# 06_-_MEMORY.net
KiCad netlist of a schematic drawn in Altium Designer
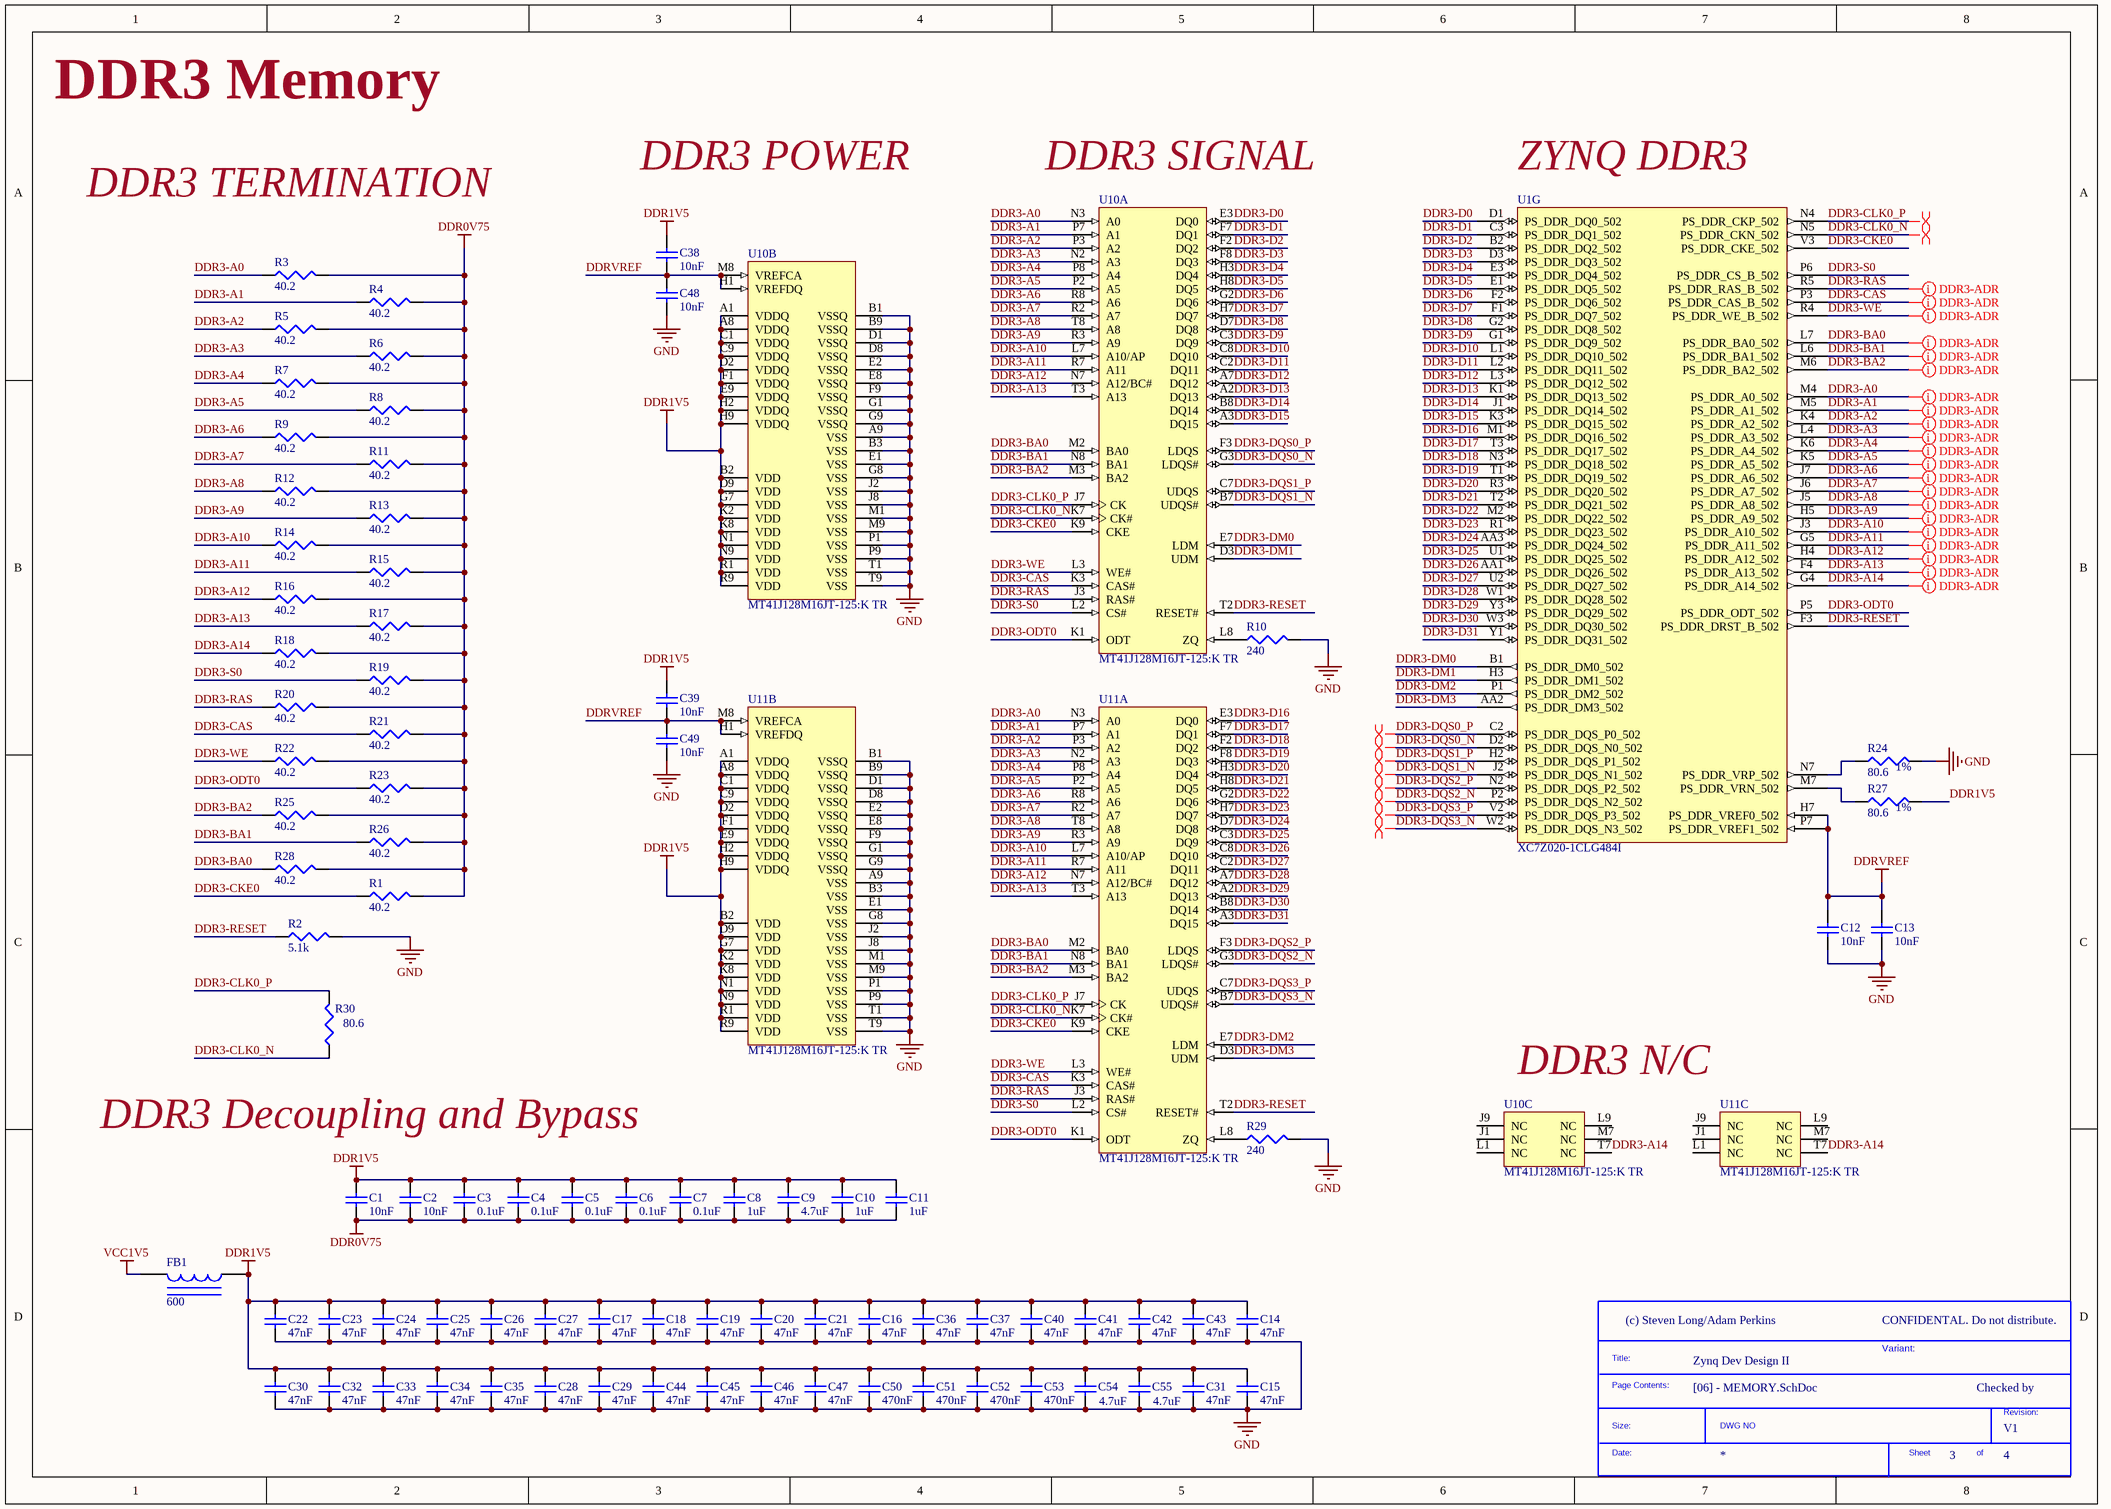
[diagram p0: [06] - MEMORY.SchDoc]

(export (version "E")
  (design (tool "Eeschema 10.0.6"))
  (components
    (comp (ref "C1")
      (value "10nF")
      (footprint "0402")
      (description "Capacitor (Semiconductor SIM Model)")
      (fields (field (name "Comment") "Capacitor") (field (name "PUBLISHER") "Altium Limited"))
      (libsource (lib "Miscellaneous Devices") (part "Cap Semi"))
    )
    (comp (ref "C2")
      (value "10nF")
      (footprint "0402")
      (description "Capacitor (Semiconductor SIM Model)")
      (fields (field (name "Comment") "Capacitor") (field (name "PUBLISHER") "Altium Limited"))
      (libsource (lib "Miscellaneous Devices") (part "Cap Semi"))
    )
    (comp (ref "C3")
      (value "0.1uF")
      (footprint "0402")
      (description "Capacitor (Semiconductor SIM Model)")
      (fields (field (name "Comment") "Capacitor") (field (name "PUBLISHER") "Altium Limited"))
      (libsource (lib "Miscellaneous Devices") (part "Cap Semi"))
    )
    (comp (ref "C4")
      (value "0.1uF")
      (footprint "0402")
      (description "Capacitor (Semiconductor SIM Model)")
      (fields (field (name "Comment") "Capacitor") (field (name "PUBLISHER") "Altium Limited"))
      (libsource (lib "Miscellaneous Devices") (part "Cap Semi"))
    )
    (comp (ref "C5")
      (value "0.1uF")
      (footprint "0402")
      (description "Capacitor (Semiconductor SIM Model)")
      (fields (field (name "Comment") "Capacitor") (field (name "PUBLISHER") "Altium Limited"))
      (libsource (lib "Miscellaneous Devices") (part "Cap Semi"))
    )
    (comp (ref "C6")
      (value "0.1uF")
      (footprint "0402")
      (description "Capacitor (Semiconductor SIM Model)")
      (fields (field (name "Comment") "Capacitor") (field (name "PUBLISHER") "Altium Limited"))
      (libsource (lib "Miscellaneous Devices") (part "Cap Semi"))
    )
    (comp (ref "C7")
      (value "0.1uF")
      (footprint "0402")
      (description "Capacitor (Semiconductor SIM Model)")
      (fields (field (name "Comment") "Capacitor") (field (name "PUBLISHER") "Altium Limited"))
      (libsource (lib "Miscellaneous Devices") (part "Cap Semi"))
    )
    (comp (ref "C8")
      (value "1uF")
      (footprint "1608[0603]")
      (description "Capacitor (Semiconductor SIM Model)")
      (fields (field (name "Comment") "Capacitor") (field (name "PUBLISHER") "Altium Limited"))
      (libsource (lib "Miscellaneous Devices") (part "Cap Semi"))
    )
    (comp (ref "C9")
      (value "4.7uF")
      (footprint "1608[0603]")
      (description "Capacitor (Semiconductor SIM Model)")
      (fields (field (name "Comment") "Capacitor") (field (name "PUBLISHER") "Altium Limited"))
      (libsource (lib "Miscellaneous Devices") (part "Cap Semi"))
    )
    (comp (ref "C10")
      (value "1uF")
      (footprint "1608[0603]")
      (description "Capacitor (Semiconductor SIM Model)")
      (fields (field (name "Comment") "Capacitor") (field (name "PUBLISHER") "Altium Limited"))
      (libsource (lib "Miscellaneous Devices") (part "Cap Semi"))
    )
    (comp (ref "C11")
      (value "1uF")
      (footprint "1608[0603]")
      (description "Capacitor (Semiconductor SIM Model)")
      (fields (field (name "Comment") "Capacitor") (field (name "PUBLISHER") "Altium Limited"))
      (libsource (lib "Miscellaneous Devices") (part "Cap Semi"))
    )
    (comp (ref "C12")
      (value "10nF")
      (footprint "0402")
      (description "Capacitor (Semiconductor SIM Model)")
      (fields (field (name "Comment") "Capacitor") (field (name "PUBLISHER") "Altium Limited"))
      (libsource (lib "Miscellaneous Devices") (part "Cap Semi"))
    )
    (comp (ref "C13")
      (value "10nF")
      (footprint "0402")
      (description "Capacitor (Semiconductor SIM Model)")
      (fields (field (name "Comment") "Capacitor") (field (name "PUBLISHER") "Altium Limited"))
      (libsource (lib "Miscellaneous Devices") (part "Cap Semi"))
    )
    (comp (ref "C14")
      (value "47nF")
      (footprint "0402")
      (description "Capacitor (Semiconductor SIM Model)")
      (fields (field (name "Comment") "Capacitor") (field (name "PUBLISHER") "Altium Limited"))
      (libsource (lib "Miscellaneous Devices") (part "Cap Semi"))
    )
    (comp (ref "C15")
      (value "47nF")
      (footprint "0402")
      (description "Capacitor (Semiconductor SIM Model)")
      (fields (field (name "Comment") "Capacitor") (field (name "PUBLISHER") "Altium Limited"))
      (libsource (lib "Miscellaneous Devices") (part "Cap Semi"))
    )
    (comp (ref "C16")
      (value "47nF")
      (footprint "0402")
      (description "Capacitor (Semiconductor SIM Model)")
      (fields (field (name "Comment") "Capacitor") (field (name "PUBLISHER") "Altium Limited"))
      (libsource (lib "Miscellaneous Devices") (part "Cap Semi"))
    )
    (comp (ref "C17")
      (value "47nF")
      (footprint "0402")
      (description "Capacitor (Semiconductor SIM Model)")
      (fields (field (name "Comment") "Capacitor") (field (name "PUBLISHER") "Altium Limited"))
      (libsource (lib "Miscellaneous Devices") (part "Cap Semi"))
    )
    (comp (ref "C18")
      (value "47nF")
      (footprint "0402")
      (description "Capacitor (Semiconductor SIM Model)")
      (fields (field (name "Comment") "Capacitor") (field (name "PUBLISHER") "Altium Limited"))
      (libsource (lib "Miscellaneous Devices") (part "Cap Semi"))
    )
    (comp (ref "C19")
      (value "47nF")
      (footprint "0402")
      (description "Capacitor (Semiconductor SIM Model)")
      (fields (field (name "Comment") "Capacitor") (field (name "PUBLISHER") "Altium Limited"))
      (libsource (lib "Miscellaneous Devices") (part "Cap Semi"))
    )
    (comp (ref "C20")
      (value "47nF")
      (footprint "0402")
      (description "Capacitor (Semiconductor SIM Model)")
      (fields (field (name "Comment") "Capacitor") (field (name "PUBLISHER") "Altium Limited"))
      (libsource (lib "Miscellaneous Devices") (part "Cap Semi"))
    )
    (comp (ref "C21")
      (value "47nF")
      (footprint "0402")
      (description "Capacitor (Semiconductor SIM Model)")
      (fields (field (name "Comment") "Capacitor") (field (name "PUBLISHER") "Altium Limited"))
      (libsource (lib "Miscellaneous Devices") (part "Cap Semi"))
    )
    (comp (ref "C22")
      (value "47nF")
      (footprint "0402")
      (description "Capacitor (Semiconductor SIM Model)")
      (fields (field (name "Comment") "Capacitor") (field (name "PUBLISHER") "Altium Limited"))
      (libsource (lib "Miscellaneous Devices") (part "Cap Semi"))
    )
    (comp (ref "C23")
      (value "47nF")
      (footprint "0402")
      (description "Capacitor (Semiconductor SIM Model)")
      (fields (field (name "Comment") "Capacitor") (field (name "PUBLISHER") "Altium Limited"))
      (libsource (lib "Miscellaneous Devices") (part "Cap Semi"))
    )
    (comp (ref "C24")
      (value "47nF")
      (footprint "0402")
      (description "Capacitor (Semiconductor SIM Model)")
      (fields (field (name "Comment") "Capacitor") (field (name "PUBLISHER") "Altium Limited"))
      (libsource (lib "Miscellaneous Devices") (part "Cap Semi"))
    )
    (comp (ref "C25")
      (value "47nF")
      (footprint "0402")
      (description "Capacitor (Semiconductor SIM Model)")
      (fields (field (name "Comment") "Capacitor") (field (name "PUBLISHER") "Altium Limited"))
      (libsource (lib "Miscellaneous Devices") (part "Cap Semi"))
    )
    (comp (ref "C26")
      (value "47nF")
      (footprint "0402")
      (description "Capacitor (Semiconductor SIM Model)")
      (fields (field (name "Comment") "Capacitor") (field (name "PUBLISHER") "Altium Limited"))
      (libsource (lib "Miscellaneous Devices") (part "Cap Semi"))
    )
    (comp (ref "C27")
      (value "47nF")
      (footprint "0402")
      (description "Capacitor (Semiconductor SIM Model)")
      (fields (field (name "Comment") "Capacitor") (field (name "PUBLISHER") "Altium Limited"))
      (libsource (lib "Miscellaneous Devices") (part "Cap Semi"))
    )
    (comp (ref "C28")
      (value "47nF")
      (footprint "0402")
      (description "Capacitor (Semiconductor SIM Model)")
      (fields (field (name "Comment") "Capacitor") (field (name "PUBLISHER") "Altium Limited"))
      (libsource (lib "Miscellaneous Devices") (part "Cap Semi"))
    )
    (comp (ref "C29")
      (value "47nF")
      (footprint "0402")
      (description "Capacitor (Semiconductor SIM Model)")
      (fields (field (name "Comment") "Capacitor") (field (name "PUBLISHER") "Altium Limited"))
      (libsource (lib "Miscellaneous Devices") (part "Cap Semi"))
    )
    (comp (ref "C30")
      (value "47nF")
      (footprint "0402")
      (description "Capacitor (Semiconductor SIM Model)")
      (fields (field (name "Comment") "Capacitor") (field (name "PUBLISHER") "Altium Limited"))
      (libsource (lib "Miscellaneous Devices") (part "Cap Semi"))
    )
    (comp (ref "C31")
      (value "47nF")
      (footprint "0402")
      (description "Capacitor (Semiconductor SIM Model)")
      (fields (field (name "Comment") "Capacitor") (field (name "PUBLISHER") "Altium Limited"))
      (libsource (lib "Miscellaneous Devices") (part "Cap Semi"))
    )
    (comp (ref "C32")
      (value "47nF")
      (footprint "0402")
      (description "Capacitor (Semiconductor SIM Model)")
      (fields (field (name "Comment") "Capacitor") (field (name "PUBLISHER") "Altium Limited"))
      (libsource (lib "Miscellaneous Devices") (part "Cap Semi"))
    )
    (comp (ref "C33")
      (value "47nF")
      (footprint "0402")
      (description "Capacitor (Semiconductor SIM Model)")
      (fields (field (name "Comment") "Capacitor") (field (name "PUBLISHER") "Altium Limited"))
      (libsource (lib "Miscellaneous Devices") (part "Cap Semi"))
    )
    (comp (ref "C34")
      (value "47nF")
      (footprint "0402")
      (description "Capacitor (Semiconductor SIM Model)")
      (fields (field (name "Comment") "Capacitor") (field (name "PUBLISHER") "Altium Limited"))
      (libsource (lib "Miscellaneous Devices") (part "Cap Semi"))
    )
    (comp (ref "C35")
      (value "47nF")
      (footprint "0402")
      (description "Capacitor (Semiconductor SIM Model)")
      (fields (field (name "Comment") "Capacitor") (field (name "PUBLISHER") "Altium Limited"))
      (libsource (lib "Miscellaneous Devices") (part "Cap Semi"))
    )
    (comp (ref "C36")
      (value "47nF")
      (footprint "0402")
      (description "Capacitor (Semiconductor SIM Model)")
      (fields (field (name "Comment") "Capacitor") (field (name "PUBLISHER") "Altium Limited"))
      (libsource (lib "Miscellaneous Devices") (part "Cap Semi"))
    )
    (comp (ref "C37")
      (value "47nF")
      (footprint "0402")
      (description "Capacitor (Semiconductor SIM Model)")
      (fields (field (name "Comment") "Capacitor") (field (name "PUBLISHER") "Altium Limited"))
      (libsource (lib "Miscellaneous Devices") (part "Cap Semi"))
    )
    (comp (ref "C38")
      (value "10nF")
      (footprint "0402")
      (description "Capacitor (Semiconductor SIM Model)")
      (fields (field (name "Comment") "Capacitor") (field (name "PUBLISHER") "Altium Limited"))
      (libsource (lib "Miscellaneous Devices") (part "Cap Semi"))
    )
    (comp (ref "C39")
      (value "10nF")
      (footprint "0402")
      (description "Capacitor (Semiconductor SIM Model)")
      (fields (field (name "Comment") "Capacitor") (field (name "PUBLISHER") "Altium Limited"))
      (libsource (lib "Miscellaneous Devices") (part "Cap Semi"))
    )
    (comp (ref "C40")
      (value "47nF")
      (footprint "0402")
      (description "Capacitor (Semiconductor SIM Model)")
      (fields (field (name "Comment") "Capacitor") (field (name "PUBLISHER") "Altium Limited"))
      (libsource (lib "Miscellaneous Devices") (part "Cap Semi"))
    )
    (comp (ref "C41")
      (value "47nF")
      (footprint "0402")
      (description "Capacitor (Semiconductor SIM Model)")
      (fields (field (name "Comment") "Capacitor") (field (name "PUBLISHER") "Altium Limited"))
      (libsource (lib "Miscellaneous Devices") (part "Cap Semi"))
    )
    (comp (ref "C42")
      (value "47nF")
      (footprint "0402")
      (description "Capacitor (Semiconductor SIM Model)")
      (fields (field (name "Comment") "Capacitor") (field (name "PUBLISHER") "Altium Limited"))
      (libsource (lib "Miscellaneous Devices") (part "Cap Semi"))
    )
    (comp (ref "C43")
      (value "47nF")
      (footprint "0402")
      (description "Capacitor (Semiconductor SIM Model)")
      (fields (field (name "Comment") "Capacitor") (field (name "PUBLISHER") "Altium Limited"))
      (libsource (lib "Miscellaneous Devices") (part "Cap Semi"))
    )
    (comp (ref "C44")
      (value "47nF")
      (footprint "0402")
      (description "Capacitor (Semiconductor SIM Model)")
      (fields (field (name "Comment") "Capacitor") (field (name "PUBLISHER") "Altium Limited"))
      (libsource (lib "Miscellaneous Devices") (part "Cap Semi"))
    )
    (comp (ref "C45")
      (value "47nF")
      (footprint "0402")
      (description "Capacitor (Semiconductor SIM Model)")
      (fields (field (name "Comment") "Capacitor") (field (name "PUBLISHER") "Altium Limited"))
      (libsource (lib "Miscellaneous Devices") (part "Cap Semi"))
    )
    (comp (ref "C46")
      (value "47nF")
      (footprint "0402")
      (description "Capacitor (Semiconductor SIM Model)")
      (fields (field (name "Comment") "Capacitor") (field (name "PUBLISHER") "Altium Limited"))
      (libsource (lib "Miscellaneous Devices") (part "Cap Semi"))
    )
    (comp (ref "C47")
      (value "47nF")
      (footprint "0402")
      (description "Capacitor (Semiconductor SIM Model)")
      (fields (field (name "Comment") "Capacitor") (field (name "PUBLISHER") "Altium Limited"))
      (libsource (lib "Miscellaneous Devices") (part "Cap Semi"))
    )
    (comp (ref "C48")
      (value "10nF")
      (footprint "0402")
      (description "Capacitor (Semiconductor SIM Model)")
      (fields (field (name "Comment") "Capacitor") (field (name "PUBLISHER") "Altium Limited"))
      (libsource (lib "Miscellaneous Devices") (part "Cap Semi"))
    )
    (comp (ref "C49")
      (value "10nF")
      (footprint "0402")
      (description "Capacitor (Semiconductor SIM Model)")
      (fields (field (name "Comment") "Capacitor") (field (name "PUBLISHER") "Altium Limited"))
      (libsource (lib "Miscellaneous Devices") (part "Cap Semi"))
    )
    (comp (ref "C50")
      (value "470nF")
      (footprint "0402")
      (description "Capacitor (Semiconductor SIM Model)")
      (fields (field (name "Comment") "Capacitor") (field (name "PUBLISHER") "Altium Limited"))
      (libsource (lib "Miscellaneous Devices") (part "Cap Semi"))
    )
    (comp (ref "C51")
      (value "470nF")
      (footprint "0402")
      (description "Capacitor (Semiconductor SIM Model)")
      (fields (field (name "Comment") "Capacitor") (field (name "PUBLISHER") "Altium Limited"))
      (libsource (lib "Miscellaneous Devices") (part "Cap Semi"))
    )
    (comp (ref "C52")
      (value "470nF")
      (footprint "0402")
      (description "Capacitor (Semiconductor SIM Model)")
      (fields (field (name "Comment") "Capacitor") (field (name "PUBLISHER") "Altium Limited"))
      (libsource (lib "Miscellaneous Devices") (part "Cap Semi"))
    )
    (comp (ref "C53")
      (value "470nF")
      (footprint "0402")
      (description "Capacitor (Semiconductor SIM Model)")
      (fields (field (name "Comment") "Capacitor") (field (name "PUBLISHER") "Altium Limited"))
      (libsource (lib "Miscellaneous Devices") (part "Cap Semi"))
    )
    (comp (ref "C54")
      (value "4.7uF")
      (footprint "1608[0603]")
      (description "Capacitor (Semiconductor SIM Model)")
      (fields (field (name "Comment") "Capacitor") (field (name "PUBLISHER") "Altium Limited"))
      (libsource (lib "Miscellaneous Devices") (part "Cap Semi"))
    )
    (comp (ref "C55")
      (value "4.7uF")
      (footprint "1608[0603]")
      (description "Capacitor (Semiconductor SIM Model)")
      (fields (field (name "Comment") "Capacitor") (field (name "PUBLISHER") "Altium Limited"))
      (libsource (lib "Miscellaneous Devices") (part "Cap Semi"))
    )
    (comp (ref "FB1")
      (value "600")
      (footprint "6-0805_N")
      (description "Magnetic-Core Inductor")
      (fields (field (name "Comment") "Ferrite Bead") (field (name "PUBLISHER") "Altium Limited"))
      (libsource (lib "Miscellaneous Devices") (part "Inductor Iron"))
    )
    (comp (ref "R1")
      (value "40.2")
      (footprint "0402")
      (description "Resistor")
      (fields (field (name "PUBLISHER") "Altium Limited"))
      (libsource (lib "Miscellaneous Devices") (part "Res3"))
    )
    (comp (ref "R2")
      (value "5.1k")
      (footprint "0402")
      (description "Resistor")
      (fields (field (name "PUBLISHER") "Altium Limited"))
      (libsource (lib "Miscellaneous Devices") (part "Res3"))
    )
    (comp (ref "R3")
      (value "40.2")
      (footprint "0402")
      (description "Resistor")
      (fields (field (name "PUBLISHER") "Altium Limited"))
      (libsource (lib "Miscellaneous Devices") (part "Res3"))
    )
    (comp (ref "R4")
      (value "40.2")
      (footprint "0402")
      (description "Resistor")
      (fields (field (name "PUBLISHER") "Altium Limited"))
      (libsource (lib "Miscellaneous Devices") (part "Res3"))
    )
    (comp (ref "R5")
      (value "40.2")
      (footprint "0402")
      (description "Resistor")
      (fields (field (name "PUBLISHER") "Altium Limited"))
      (libsource (lib "Miscellaneous Devices") (part "Res3"))
    )
    (comp (ref "R6")
      (value "40.2")
      (footprint "0402")
      (description "Resistor")
      (fields (field (name "PUBLISHER") "Altium Limited"))
      (libsource (lib "Miscellaneous Devices") (part "Res3"))
    )
    (comp (ref "R7")
      (value "40.2")
      (footprint "0402")
      (description "Resistor")
      (fields (field (name "PUBLISHER") "Altium Limited"))
      (libsource (lib "Miscellaneous Devices") (part "Res3"))
    )
    (comp (ref "R8")
      (value "40.2")
      (footprint "0402")
      (description "Resistor")
      (fields (field (name "PUBLISHER") "Altium Limited"))
      (libsource (lib "Miscellaneous Devices") (part "Res3"))
    )
    (comp (ref "R9")
      (value "40.2")
      (footprint "0402")
      (description "Resistor")
      (fields (field (name "PUBLISHER") "Altium Limited"))
      (libsource (lib "Miscellaneous Devices") (part "Res3"))
    )
    (comp (ref "R10")
      (value "240")
      (footprint "0402")
      (description "Resistor")
      (fields (field (name "PUBLISHER") "Altium Limited"))
      (libsource (lib "Miscellaneous Devices") (part "Res3"))
    )
    (comp (ref "R11")
      (value "40.2")
      (footprint "0402")
      (description "Resistor")
      (fields (field (name "PUBLISHER") "Altium Limited"))
      (libsource (lib "Miscellaneous Devices") (part "Res3"))
    )
    (comp (ref "R12")
      (value "40.2")
      (footprint "0402")
      (description "Resistor")
      (fields (field (name "PUBLISHER") "Altium Limited"))
      (libsource (lib "Miscellaneous Devices") (part "Res3"))
    )
    (comp (ref "R13")
      (value "40.2")
      (footprint "0402")
      (description "Resistor")
      (fields (field (name "PUBLISHER") "Altium Limited"))
      (libsource (lib "Miscellaneous Devices") (part "Res3"))
    )
    (comp (ref "R14")
      (value "40.2")
      (footprint "0402")
      (description "Resistor")
      (fields (field (name "PUBLISHER") "Altium Limited"))
      (libsource (lib "Miscellaneous Devices") (part "Res3"))
    )
    (comp (ref "R15")
      (value "40.2")
      (footprint "0402")
      (description "Resistor")
      (fields (field (name "PUBLISHER") "Altium Limited"))
      (libsource (lib "Miscellaneous Devices") (part "Res3"))
    )
    (comp (ref "R16")
      (value "40.2")
      (footprint "0402")
      (description "Resistor")
      (fields (field (name "PUBLISHER") "Altium Limited"))
      (libsource (lib "Miscellaneous Devices") (part "Res3"))
    )
    (comp (ref "R17")
      (value "40.2")
      (footprint "0402")
      (description "Resistor")
      (fields (field (name "PUBLISHER") "Altium Limited"))
      (libsource (lib "Miscellaneous Devices") (part "Res3"))
    )
    (comp (ref "R18")
      (value "40.2")
      (footprint "0402")
      (description "Resistor")
      (fields (field (name "PUBLISHER") "Altium Limited"))
      (libsource (lib "Miscellaneous Devices") (part "Res3"))
    )
    (comp (ref "R19")
      (value "40.2")
      (footprint "0402")
      (description "Resistor")
      (fields (field (name "PUBLISHER") "Altium Limited"))
      (libsource (lib "Miscellaneous Devices") (part "Res3"))
    )
    (comp (ref "R20")
      (value "40.2")
      (footprint "0402")
      (description "Resistor")
      (fields (field (name "PUBLISHER") "Altium Limited"))
      (libsource (lib "Miscellaneous Devices") (part "Res3"))
    )
    (comp (ref "R21")
      (value "40.2")
      (footprint "0402")
      (description "Resistor")
      (fields (field (name "PUBLISHER") "Altium Limited"))
      (libsource (lib "Miscellaneous Devices") (part "Res3"))
    )
    (comp (ref "R22")
      (value "40.2")
      (footprint "0402")
      (description "Resistor")
      (fields (field (name "PUBLISHER") "Altium Limited"))
      (libsource (lib "Miscellaneous Devices") (part "Res3"))
    )
    (comp (ref "R23")
      (value "40.2")
      (footprint "0402")
      (description "Resistor")
      (fields (field (name "PUBLISHER") "Altium Limited"))
      (libsource (lib "Miscellaneous Devices") (part "Res3"))
    )
    (comp (ref "R24")
      (value "80.6")
      (footprint "0402")
      (description "Resistor")
      (fields (field (name "TOLERANCE") "1%") (field (name "PUBLISHER") "Altium Limited"))
      (libsource (lib "Miscellaneous Devices") (part "Res3"))
    )
    (comp (ref "R25")
      (value "40.2")
      (footprint "0402")
      (description "Resistor")
      (fields (field (name "PUBLISHER") "Altium Limited"))
      (libsource (lib "Miscellaneous Devices") (part "Res3"))
    )
    (comp (ref "R26")
      (value "40.2")
      (footprint "0402")
      (description "Resistor")
      (fields (field (name "PUBLISHER") "Altium Limited"))
      (libsource (lib "Miscellaneous Devices") (part "Res3"))
    )
    (comp (ref "R27")
      (value "80.6")
      (footprint "0402")
      (description "Resistor")
      (fields (field (name "TOLERANCE") "1%") (field (name "PUBLISHER") "Altium Limited"))
      (libsource (lib "Miscellaneous Devices") (part "Res3"))
    )
    (comp (ref "R28")
      (value "40.2")
      (footprint "0402")
      (description "Resistor")
      (fields (field (name "PUBLISHER") "Altium Limited"))
      (libsource (lib "Miscellaneous Devices") (part "Res3"))
    )
    (comp (ref "R29")
      (value "240")
      (footprint "0402")
      (description "Resistor")
      (fields (field (name "PUBLISHER") "Altium Limited"))
      (libsource (lib "Miscellaneous Devices") (part "Res3"))
    )
    (comp (ref "R30")
      (value "80.6")
      (footprint "0402")
      (description "Resistor")
      (fields (field (name "TOLERANCE") "1%") (field (name "PUBLISHER") "Altium Limited"))
      (libsource (lib "Miscellaneous Devices") (part "Res3"))
    )
    (comp (ref "U1")
      (value "XC7Z020-1CLG484I")
      (footprint "CLG484")
      (description "IC SOC CORTEX-A9 ARTIX-7 484BGA")
      (fields (field (name "MANUFACTURER") "Xilinx Inc."))
      (libsource (lib "zynq_dev_V1") (part "XC7Z020-1CLG484I"))
    )
    (comp (ref "U10")
      (value "MT41J128M16JT-125:K TR")
      (footprint "MICT-JT-96")
      (description "IC DDR3 SDRAM 2GBIT 96FBGA")
      (fields (field (name "MANUFACTURER") "Micron Technology Inc."))
      (libsource (lib "zynq_dev_V1") (part "MT41J128M16JT-125{colon}K TR"))
    )
    (comp (ref "U11")
      (value "MT41J128M16JT-125:K TR")
      (footprint "MICT-JT-96")
      (description "IC DDR3 SDRAM 2GBIT 96FBGA")
      (fields (field (name "MANUFACTURER") "Micron Technology Inc."))
      (libsource (lib "zynq_dev_V1") (part "MT41J128M16JT-125{colon}K TR"))
    )
  )
  (nets
    (net (code "1") (name "/DDR3-A0") (class "Default")
      (node (ref "R3") (pin "1") (pinfunction "1_1") (pintype "passive"))
      (node (ref "U1") (pin "M4") (pinfunction "PS_DDR_A0_502_M4") (pintype "output"))
      (node (ref "U10") (pin "N3") (pinfunction "A0_N3") (pintype "input"))
      (node (ref "U11") (pin "N3") (pinfunction "A0_N3") (pintype "input"))
    )
    (net (code "2") (name "/DDR3-A1") (class "Default")
      (node (ref "R4") (pin "1") (pinfunction "1_1") (pintype "passive"))
      (node (ref "U1") (pin "M5") (pinfunction "PS_DDR_A1_502_M5") (pintype "output"))
      (node (ref "U10") (pin "P7") (pinfunction "A1_P7") (pintype "input"))
      (node (ref "U11") (pin "P7") (pinfunction "A1_P7") (pintype "input"))
    )
    (net (code "3") (name "/DDR3-A2") (class "Default")
      (node (ref "R5") (pin "1") (pinfunction "1_1") (pintype "passive"))
      (node (ref "U1") (pin "K4") (pinfunction "PS_DDR_A2_502_K4") (pintype "output"))
      (node (ref "U10") (pin "P3") (pinfunction "A2_P3") (pintype "input"))
      (node (ref "U11") (pin "P3") (pinfunction "A2_P3") (pintype "input"))
    )
    (net (code "4") (name "/DDR3-A3") (class "Default")
      (node (ref "R6") (pin "1") (pinfunction "1_1") (pintype "passive"))
      (node (ref "U1") (pin "L4") (pinfunction "PS_DDR_A3_502_L4") (pintype "output"))
      (node (ref "U10") (pin "N2") (pinfunction "A3_N2") (pintype "input"))
      (node (ref "U11") (pin "N2") (pinfunction "A3_N2") (pintype "input"))
    )
    (net (code "5") (name "/DDR3-A4") (class "Default")
      (node (ref "R7") (pin "1") (pinfunction "1_1") (pintype "passive"))
      (node (ref "U1") (pin "K6") (pinfunction "PS_DDR_A4_502_K6") (pintype "output"))
      (node (ref "U10") (pin "P8") (pinfunction "A4_P8") (pintype "input"))
      (node (ref "U11") (pin "P8") (pinfunction "A4_P8") (pintype "input"))
    )
    (net (code "6") (name "/DDR3-A5") (class "Default")
      (node (ref "R8") (pin "1") (pinfunction "1_1") (pintype "passive"))
      (node (ref "U1") (pin "K5") (pinfunction "PS_DDR_A5_502_K5") (pintype "output"))
      (node (ref "U10") (pin "P2") (pinfunction "A5_P2") (pintype "input"))
      (node (ref "U11") (pin "P2") (pinfunction "A5_P2") (pintype "input"))
    )
    (net (code "7") (name "/DDR3-A6") (class "Default")
      (node (ref "R9") (pin "1") (pinfunction "1_1") (pintype "passive"))
      (node (ref "U1") (pin "J7") (pinfunction "PS_DDR_A6_502_J7") (pintype "output"))
      (node (ref "U10") (pin "R8") (pinfunction "A6_R8") (pintype "input"))
      (node (ref "U11") (pin "R8") (pinfunction "A6_R8") (pintype "input"))
    )
    (net (code "8") (name "/DDR3-A7") (class "Default")
      (node (ref "R11") (pin "1") (pinfunction "1_1") (pintype "passive"))
      (node (ref "U1") (pin "J6") (pinfunction "PS_DDR_A7_502_J6") (pintype "output"))
      (node (ref "U10") (pin "R2") (pinfunction "A7_R2") (pintype "input"))
      (node (ref "U11") (pin "R2") (pinfunction "A7_R2") (pintype "input"))
    )
    (net (code "9") (name "/DDR3-A8") (class "Default")
      (node (ref "R12") (pin "1") (pinfunction "1_1") (pintype "passive"))
      (node (ref "U1") (pin "J5") (pinfunction "PS_DDR_A8_502_J5") (pintype "output"))
      (node (ref "U10") (pin "T8") (pinfunction "A8_T8") (pintype "input"))
      (node (ref "U11") (pin "T8") (pinfunction "A8_T8") (pintype "input"))
    )
    (net (code "10") (name "/DDR3-A9") (class "Default")
      (node (ref "R13") (pin "1") (pinfunction "1_1") (pintype "passive"))
      (node (ref "U1") (pin "H5") (pinfunction "PS_DDR_A9_502_H5") (pintype "output"))
      (node (ref "U10") (pin "R3") (pinfunction "A9_R3") (pintype "input"))
      (node (ref "U11") (pin "R3") (pinfunction "A9_R3") (pintype "input"))
    )
    (net (code "11") (name "/DDR3-A10") (class "Default")
      (node (ref "R14") (pin "1") (pinfunction "1_1") (pintype "passive"))
      (node (ref "U1") (pin "J3") (pinfunction "PS_DDR_A10_502_J3") (pintype "output"))
      (node (ref "U10") (pin "L7") (pinfunction "A10/AP_L7") (pintype "input"))
      (node (ref "U11") (pin "L7") (pinfunction "A10/AP_L7") (pintype "input"))
    )
    (net (code "12") (name "/DDR3-A11") (class "Default")
      (node (ref "R15") (pin "1") (pinfunction "1_1") (pintype "passive"))
      (node (ref "U1") (pin "G5") (pinfunction "PS_DDR_A11_502_G5") (pintype "output"))
      (node (ref "U10") (pin "R7") (pinfunction "A11_R7") (pintype "input"))
      (node (ref "U11") (pin "R7") (pinfunction "A11_R7") (pintype "input"))
    )
    (net (code "13") (name "/DDR3-A12") (class "Default")
      (node (ref "R16") (pin "1") (pinfunction "1_1") (pintype "passive"))
      (node (ref "U1") (pin "H4") (pinfunction "PS_DDR_A12_502_H4") (pintype "output"))
      (node (ref "U10") (pin "N7") (pinfunction "A12/BC#_N7") (pintype "input"))
      (node (ref "U11") (pin "N7") (pinfunction "A12/BC#_N7") (pintype "input"))
    )
    (net (code "14") (name "/DDR3-A13") (class "Default")
      (node (ref "R17") (pin "1") (pinfunction "1_1") (pintype "passive"))
      (node (ref "U1") (pin "F4") (pinfunction "PS_DDR_A13_502_F4") (pintype "output"))
      (node (ref "U10") (pin "T3") (pinfunction "A13_T3") (pintype "input"))
      (node (ref "U11") (pin "T3") (pinfunction "A13_T3") (pintype "input"))
    )
    (net (code "15") (name "/DDR3-A14") (class "Default")
      (node (ref "R18") (pin "1") (pinfunction "1_1") (pintype "passive"))
      (node (ref "U1") (pin "G4") (pinfunction "PS_DDR_A14_502_G4") (pintype "output"))
      (node (ref "U10") (pin "T7") (pinfunction "NC_T7") (pintype "passive"))
      (node (ref "U11") (pin "T7") (pinfunction "NC_T7") (pintype "passive"))
    )
    (net (code "16") (name "/DDR3-BA0") (class "Default")
      (node (ref "R28") (pin "1") (pinfunction "1_1") (pintype "passive"))
      (node (ref "U1") (pin "L7") (pinfunction "PS_DDR_BA0_502_L7") (pintype "output"))
      (node (ref "U10") (pin "M2") (pinfunction "BA0_M2") (pintype "input"))
      (node (ref "U11") (pin "M2") (pinfunction "BA0_M2") (pintype "input"))
    )
    (net (code "17") (name "/DDR3-BA1") (class "Default")
      (node (ref "R26") (pin "1") (pinfunction "1_1") (pintype "passive"))
      (node (ref "U1") (pin "L6") (pinfunction "PS_DDR_BA1_502_L6") (pintype "output"))
      (node (ref "U10") (pin "N8") (pinfunction "BA1_N8") (pintype "input"))
      (node (ref "U11") (pin "N8") (pinfunction "BA1_N8") (pintype "input"))
    )
    (net (code "18") (name "/DDR3-BA2") (class "Default")
      (node (ref "R25") (pin "1") (pinfunction "1_1") (pintype "passive"))
      (node (ref "U1") (pin "M6") (pinfunction "PS_DDR_BA2_502_M6") (pintype "output"))
      (node (ref "U10") (pin "M3") (pinfunction "BA2_M3") (pintype "input"))
      (node (ref "U11") (pin "M3") (pinfunction "BA2_M3") (pintype "input"))
    )
    (net (code "19") (name "/DDR3-CAS") (class "Default")
      (node (ref "R21") (pin "1") (pinfunction "1_1") (pintype "passive"))
      (node (ref "U1") (pin "P3") (pinfunction "PS_DDR_CAS_B_502_P3") (pintype "output"))
      (node (ref "U10") (pin "K3") (pinfunction "CAS#_K3") (pintype "input"))
      (node (ref "U11") (pin "K3") (pinfunction "CAS#_K3") (pintype "input"))
    )
    (net (code "20") (name "/DDR3-CKE0") (class "Default")
      (node (ref "R1") (pin "1") (pinfunction "1_1") (pintype "passive"))
      (node (ref "U1") (pin "V3") (pinfunction "PS_DDR_CKE_502_V3") (pintype "output"))
      (node (ref "U10") (pin "K9") (pinfunction "CKE_K9") (pintype "input"))
      (node (ref "U11") (pin "K9") (pinfunction "CKE_K9") (pintype "input"))
    )
    (net (code "21") (name "/DDR3-CLK0_N") (class "Default")
      (node (ref "R30") (pin "1") (pinfunction "1_1") (pintype "passive"))
      (node (ref "U1") (pin "N5") (pinfunction "PS_DDR_CKN_502_N5") (pintype "output"))
      (node (ref "U10") (pin "K7") (pinfunction "CK#_K7") (pintype "input"))
      (node (ref "U11") (pin "K7") (pinfunction "CK#_K7") (pintype "input"))
    )
    (net (code "22") (name "/DDR3-CLK0_P") (class "Default")
      (node (ref "R30") (pin "2") (pinfunction "2_2") (pintype "passive"))
      (node (ref "U1") (pin "N4") (pinfunction "PS_DDR_CKP_502_N4") (pintype "output"))
      (node (ref "U10") (pin "J7") (pinfunction "CK_J7") (pintype "input"))
      (node (ref "U11") (pin "J7") (pinfunction "CK_J7") (pintype "input"))
    )
    (net (code "23") (name "/DDR3-D0") (class "Default")
      (node (ref "U1") (pin "D1") (pinfunction "PS_DDR_DQ0_502_D1") (pintype "bidirectional"))
      (node (ref "U10") (pin "E3") (pinfunction "DQ0_E3") (pintype "bidirectional"))
    )
    (net (code "24") (name "/DDR3-D1") (class "Default")
      (node (ref "U1") (pin "C3") (pinfunction "PS_DDR_DQ1_502_C3") (pintype "bidirectional"))
      (node (ref "U10") (pin "F7") (pinfunction "DQ1_F7") (pintype "bidirectional"))
    )
    (net (code "25") (name "/DDR3-D2") (class "Default")
      (node (ref "U1") (pin "B2") (pinfunction "PS_DDR_DQ2_502_B2") (pintype "bidirectional"))
      (node (ref "U10") (pin "F2") (pinfunction "DQ2_F2") (pintype "bidirectional"))
    )
    (net (code "26") (name "/DDR3-D3") (class "Default")
      (node (ref "U1") (pin "D3") (pinfunction "PS_DDR_DQ3_502_D3") (pintype "bidirectional"))
      (node (ref "U10") (pin "F8") (pinfunction "DQ3_F8") (pintype "bidirectional"))
    )
    (net (code "27") (name "/DDR3-D4") (class "Default")
      (node (ref "U1") (pin "E3") (pinfunction "PS_DDR_DQ4_502_E3") (pintype "bidirectional"))
      (node (ref "U10") (pin "H3") (pinfunction "DQ4_H3") (pintype "bidirectional"))
    )
    (net (code "28") (name "/DDR3-D5") (class "Default")
      (node (ref "U1") (pin "E1") (pinfunction "PS_DDR_DQ5_502_E1") (pintype "bidirectional"))
      (node (ref "U10") (pin "H8") (pinfunction "DQ5_H8") (pintype "bidirectional"))
    )
    (net (code "29") (name "/DDR3-D6") (class "Default")
      (node (ref "U1") (pin "F2") (pinfunction "PS_DDR_DQ6_502_F2") (pintype "bidirectional"))
      (node (ref "U10") (pin "G2") (pinfunction "DQ6_G2") (pintype "bidirectional"))
    )
    (net (code "30") (name "/DDR3-D7") (class "Default")
      (node (ref "U1") (pin "F1") (pinfunction "PS_DDR_DQ7_502_F1") (pintype "bidirectional"))
      (node (ref "U10") (pin "H7") (pinfunction "DQ7_H7") (pintype "bidirectional"))
    )
    (net (code "31") (name "/DDR3-D8") (class "Default")
      (node (ref "U1") (pin "G2") (pinfunction "PS_DDR_DQ8_502_G2") (pintype "bidirectional"))
      (node (ref "U10") (pin "D7") (pinfunction "DQ8_D7") (pintype "bidirectional"))
    )
    (net (code "32") (name "/DDR3-D9") (class "Default")
      (node (ref "U1") (pin "G1") (pinfunction "PS_DDR_DQ9_502_G1") (pintype "bidirectional"))
      (node (ref "U10") (pin "C3") (pinfunction "DQ9_C3") (pintype "bidirectional"))
    )
    (net (code "33") (name "/DDR3-D10") (class "Default")
      (node (ref "U1") (pin "L1") (pinfunction "PS_DDR_DQ10_502_L1") (pintype "bidirectional"))
      (node (ref "U10") (pin "C8") (pinfunction "DQ10_C8") (pintype "bidirectional"))
    )
    (net (code "34") (name "/DDR3-D11") (class "Default")
      (node (ref "U1") (pin "L2") (pinfunction "PS_DDR_DQ11_502_L2") (pintype "bidirectional"))
      (node (ref "U10") (pin "C2") (pinfunction "DQ11_C2") (pintype "bidirectional"))
    )
    (net (code "35") (name "/DDR3-D12") (class "Default")
      (node (ref "U1") (pin "L3") (pinfunction "PS_DDR_DQ12_502_L3") (pintype "bidirectional"))
      (node (ref "U10") (pin "A7") (pinfunction "DQ12_A7") (pintype "bidirectional"))
    )
    (net (code "36") (name "/DDR3-D13") (class "Default")
      (node (ref "U1") (pin "K1") (pinfunction "PS_DDR_DQ13_502_K1") (pintype "bidirectional"))
      (node (ref "U10") (pin "A2") (pinfunction "DQ13_A2") (pintype "bidirectional"))
    )
    (net (code "37") (name "/DDR3-D14") (class "Default")
      (node (ref "U1") (pin "J1") (pinfunction "PS_DDR_DQ14_502_J1") (pintype "bidirectional"))
      (node (ref "U10") (pin "B8") (pinfunction "DQ14_B8") (pintype "bidirectional"))
    )
    (net (code "38") (name "/DDR3-D15") (class "Default")
      (node (ref "U1") (pin "K3") (pinfunction "PS_DDR_DQ15_502_K3") (pintype "bidirectional"))
      (node (ref "U10") (pin "A3") (pinfunction "DQ15_A3") (pintype "bidirectional"))
    )
    (net (code "39") (name "/DDR3-D16") (class "Default")
      (node (ref "U1") (pin "M1") (pinfunction "PS_DDR_DQ16_502_M1") (pintype "bidirectional"))
      (node (ref "U11") (pin "E3") (pinfunction "DQ0_E3") (pintype "bidirectional"))
    )
    (net (code "40") (name "/DDR3-D17") (class "Default")
      (node (ref "U1") (pin "T3") (pinfunction "PS_DDR_DQ17_502_T3") (pintype "bidirectional"))
      (node (ref "U11") (pin "F7") (pinfunction "DQ1_F7") (pintype "bidirectional"))
    )
    (net (code "41") (name "/DDR3-D18") (class "Default")
      (node (ref "U1") (pin "N3") (pinfunction "PS_DDR_DQ18_502_N3") (pintype "bidirectional"))
      (node (ref "U11") (pin "F2") (pinfunction "DQ2_F2") (pintype "bidirectional"))
    )
    (net (code "42") (name "/DDR3-D19") (class "Default")
      (node (ref "U1") (pin "T1") (pinfunction "PS_DDR_DQ19_502_T1") (pintype "bidirectional"))
      (node (ref "U11") (pin "F8") (pinfunction "DQ3_F8") (pintype "bidirectional"))
    )
    (net (code "43") (name "/DDR3-D20") (class "Default")
      (node (ref "U1") (pin "R3") (pinfunction "PS_DDR_DQ20_502_R3") (pintype "bidirectional"))
      (node (ref "U11") (pin "H3") (pinfunction "DQ4_H3") (pintype "bidirectional"))
    )
    (net (code "44") (name "/DDR3-D21") (class "Default")
      (node (ref "U1") (pin "T2") (pinfunction "PS_DDR_DQ21_502_T2") (pintype "bidirectional"))
      (node (ref "U11") (pin "H8") (pinfunction "DQ5_H8") (pintype "bidirectional"))
    )
    (net (code "45") (name "/DDR3-D22") (class "Default")
      (node (ref "U1") (pin "M2") (pinfunction "PS_DDR_DQ22_502_M2") (pintype "bidirectional"))
      (node (ref "U11") (pin "G2") (pinfunction "DQ6_G2") (pintype "bidirectional"))
    )
    (net (code "46") (name "/DDR3-D23") (class "Default")
      (node (ref "U1") (pin "R1") (pinfunction "PS_DDR_DQ23_502_R1") (pintype "bidirectional"))
      (node (ref "U11") (pin "H7") (pinfunction "DQ7_H7") (pintype "bidirectional"))
    )
    (net (code "47") (name "/DDR3-D24") (class "Default")
      (node (ref "U1") (pin "AA3") (pinfunction "PS_DDR_DQ24_502_AA3") (pintype "bidirectional"))
      (node (ref "U11") (pin "D7") (pinfunction "DQ8_D7") (pintype "bidirectional"))
    )
    (net (code "48") (name "/DDR3-D25") (class "Default")
      (node (ref "U1") (pin "U1") (pinfunction "PS_DDR_DQ25_502_U1") (pintype "bidirectional"))
      (node (ref "U11") (pin "C3") (pinfunction "DQ9_C3") (pintype "bidirectional"))
    )
    (net (code "49") (name "/DDR3-D26") (class "Default")
      (node (ref "U1") (pin "AA1") (pinfunction "PS_DDR_DQ26_502_AA1") (pintype "bidirectional"))
      (node (ref "U11") (pin "C8") (pinfunction "DQ10_C8") (pintype "bidirectional"))
    )
    (net (code "50") (name "/DDR3-D27") (class "Default")
      (node (ref "U1") (pin "U2") (pinfunction "PS_DDR_DQ27_502_U2") (pintype "bidirectional"))
      (node (ref "U11") (pin "C2") (pinfunction "DQ11_C2") (pintype "bidirectional"))
    )
    (net (code "51") (name "/DDR3-D28") (class "Default")
      (node (ref "U1") (pin "W1") (pinfunction "PS_DDR_DQ28_502_W1") (pintype "bidirectional"))
      (node (ref "U11") (pin "A7") (pinfunction "DQ12_A7") (pintype "bidirectional"))
    )
    (net (code "52") (name "/DDR3-D29") (class "Default")
      (node (ref "U1") (pin "Y3") (pinfunction "PS_DDR_DQ29_502_Y3") (pintype "bidirectional"))
      (node (ref "U11") (pin "A2") (pinfunction "DQ13_A2") (pintype "bidirectional"))
    )
    (net (code "53") (name "/DDR3-D30") (class "Default")
      (node (ref "U1") (pin "W3") (pinfunction "PS_DDR_DQ30_502_W3") (pintype "bidirectional"))
      (node (ref "U11") (pin "B8") (pinfunction "DQ14_B8") (pintype "bidirectional"))
    )
    (net (code "54") (name "/DDR3-D31") (class "Default")
      (node (ref "U1") (pin "Y1") (pinfunction "PS_DDR_DQ31_502_Y1") (pintype "bidirectional"))
      (node (ref "U11") (pin "A3") (pinfunction "DQ15_A3") (pintype "bidirectional"))
    )
    (net (code "55") (name "/DDR3-DM0") (class "Default")
      (node (ref "U1") (pin "B1") (pinfunction "PS_DDR_DM0_502_B1") (pintype "output"))
      (node (ref "U10") (pin "E7") (pinfunction "LDM_E7") (pintype "input"))
    )
    (net (code "56") (name "/DDR3-DM1") (class "Default")
      (node (ref "U1") (pin "H3") (pinfunction "PS_DDR_DM1_502_H3") (pintype "output"))
      (node (ref "U10") (pin "D3") (pinfunction "UDM_D3") (pintype "input"))
    )
    (net (code "57") (name "/DDR3-DM2") (class "Default")
      (node (ref "U1") (pin "P1") (pinfunction "PS_DDR_DM2_502_P1") (pintype "output"))
      (node (ref "U11") (pin "E7") (pinfunction "LDM_E7") (pintype "input"))
    )
    (net (code "58") (name "/DDR3-DM3") (class "Default")
      (node (ref "U1") (pin "AA2") (pinfunction "PS_DDR_DM3_502_AA2") (pintype "output"))
      (node (ref "U11") (pin "D3") (pinfunction "UDM_D3") (pintype "input"))
    )
    (net (code "59") (name "/DDR3-DQS0_N") (class "Default")
      (node (ref "U1") (pin "D2") (pinfunction "PS_DDR_DQS_N0_502_D2") (pintype "bidirectional"))
      (node (ref "U10") (pin "G3") (pinfunction "LDQS#_G3") (pintype "bidirectional"))
    )
    (net (code "60") (name "/DDR3-DQS0_P") (class "Default")
      (node (ref "U1") (pin "C2") (pinfunction "PS_DDR_DQS_P0_502_C2") (pintype "bidirectional"))
      (node (ref "U10") (pin "F3") (pinfunction "LDQS_F3") (pintype "bidirectional"))
    )
    (net (code "61") (name "/DDR3-DQS1_N") (class "Default")
      (node (ref "U1") (pin "J2") (pinfunction "PS_DDR_DQS_N1_502_J2") (pintype "bidirectional"))
      (node (ref "U10") (pin "B7") (pinfunction "UDQS#_B7") (pintype "bidirectional"))
    )
    (net (code "62") (name "/DDR3-DQS1_P") (class "Default")
      (node (ref "U1") (pin "H2") (pinfunction "PS_DDR_DQS_P1_502_H2") (pintype "bidirectional"))
      (node (ref "U10") (pin "C7") (pinfunction "UDQS_C7") (pintype "bidirectional"))
    )
    (net (code "63") (name "/DDR3-DQS2_N") (class "Default")
      (node (ref "U1") (pin "P2") (pinfunction "PS_DDR_DQS_N2_502_P2") (pintype "bidirectional"))
      (node (ref "U11") (pin "G3") (pinfunction "LDQS#_G3") (pintype "bidirectional"))
    )
    (net (code "64") (name "/DDR3-DQS2_P") (class "Default")
      (node (ref "U1") (pin "N2") (pinfunction "PS_DDR_DQS_P2_502_N2") (pintype "bidirectional"))
      (node (ref "U11") (pin "F3") (pinfunction "LDQS_F3") (pintype "bidirectional"))
    )
    (net (code "65") (name "/DDR3-DQS3_N") (class "Default")
      (node (ref "U1") (pin "W2") (pinfunction "PS_DDR_DQS_N3_502_W2") (pintype "bidirectional"))
      (node (ref "U11") (pin "B7") (pinfunction "UDQS#_B7") (pintype "bidirectional"))
    )
    (net (code "66") (name "/DDR3-DQS3_P") (class "Default")
      (node (ref "U1") (pin "V2") (pinfunction "PS_DDR_DQS_P3_502_V2") (pintype "bidirectional"))
      (node (ref "U11") (pin "C7") (pinfunction "UDQS_C7") (pintype "bidirectional"))
    )
    (net (code "67") (name "/DDR3-ODT0") (class "Default")
      (node (ref "R23") (pin "1") (pinfunction "1_1") (pintype "passive"))
      (node (ref "U1") (pin "P5") (pinfunction "PS_DDR_ODT_502_P5") (pintype "output"))
      (node (ref "U10") (pin "K1") (pinfunction "ODT_K1") (pintype "input"))
      (node (ref "U11") (pin "K1") (pinfunction "ODT_K1") (pintype "input"))
    )
    (net (code "68") (name "/DDR3-RAS") (class "Default")
      (node (ref "R20") (pin "1") (pinfunction "1_1") (pintype "passive"))
      (node (ref "U1") (pin "R5") (pinfunction "PS_DDR_RAS_B_502_R5") (pintype "output"))
      (node (ref "U10") (pin "J3") (pinfunction "RAS#_J3") (pintype "input"))
      (node (ref "U11") (pin "J3") (pinfunction "RAS#_J3") (pintype "input"))
    )
    (net (code "69") (name "/DDR3-RESET") (class "Default")
      (node (ref "R2") (pin "1") (pinfunction "1_1") (pintype "passive"))
      (node (ref "U1") (pin "F3") (pinfunction "PS_DDR_DRST_B_502_F3") (pintype "output"))
      (node (ref "U10") (pin "T2") (pinfunction "RESET#_T2") (pintype "input"))
      (node (ref "U11") (pin "T2") (pinfunction "RESET#_T2") (pintype "input"))
    )
    (net (code "70") (name "/DDR3-S0") (class "Default")
      (node (ref "R19") (pin "1") (pinfunction "1_1") (pintype "passive"))
      (node (ref "U1") (pin "P6") (pinfunction "PS_DDR_CS_B_502_P6") (pintype "output"))
      (node (ref "U10") (pin "L2") (pinfunction "CS#_L2") (pintype "input"))
      (node (ref "U11") (pin "L2") (pinfunction "CS#_L2") (pintype "input"))
    )
    (net (code "71") (name "/DDR3-WE") (class "Default")
      (node (ref "R22") (pin "1") (pinfunction "1_1") (pintype "passive"))
      (node (ref "U1") (pin "R4") (pinfunction "PS_DDR_WE_B_502_R4") (pintype "output"))
      (node (ref "U10") (pin "L3") (pinfunction "WE#_L3") (pintype "input"))
      (node (ref "U11") (pin "L3") (pinfunction "WE#_L3") (pintype "input"))
    )
    (net (code "72") (name "DDR0V75") (class "Default")
      (node (ref "C1") (pin "1") (pinfunction "1_1") (pintype "passive"))
      (node (ref "C10") (pin "1") (pinfunction "1_1") (pintype "passive"))
      (node (ref "C11") (pin "1") (pinfunction "1_1") (pintype "passive"))
      (node (ref "C2") (pin "1") (pinfunction "1_1") (pintype "passive"))
      (node (ref "C3") (pin "1") (pinfunction "1_1") (pintype "passive"))
      (node (ref "C4") (pin "1") (pinfunction "1_1") (pintype "passive"))
      (node (ref "C5") (pin "1") (pinfunction "1_1") (pintype "passive"))
      (node (ref "C6") (pin "1") (pinfunction "1_1") (pintype "passive"))
      (node (ref "C7") (pin "1") (pinfunction "1_1") (pintype "passive"))
      (node (ref "C8") (pin "1") (pinfunction "1_1") (pintype "passive"))
      (node (ref "C9") (pin "1") (pinfunction "1_1") (pintype "passive"))
      (node (ref "R1") (pin "2") (pinfunction "2_2") (pintype "passive"))
      (node (ref "R11") (pin "2") (pinfunction "2_2") (pintype "passive"))
      (node (ref "R12") (pin "2") (pinfunction "2_2") (pintype "passive"))
      (node (ref "R13") (pin "2") (pinfunction "2_2") (pintype "passive"))
      (node (ref "R14") (pin "2") (pinfunction "2_2") (pintype "passive"))
      (node (ref "R15") (pin "2") (pinfunction "2_2") (pintype "passive"))
      (node (ref "R16") (pin "2") (pinfunction "2_2") (pintype "passive"))
      (node (ref "R17") (pin "2") (pinfunction "2_2") (pintype "passive"))
      (node (ref "R18") (pin "2") (pinfunction "2_2") (pintype "passive"))
      (node (ref "R19") (pin "2") (pinfunction "2_2") (pintype "passive"))
      (node (ref "R20") (pin "2") (pinfunction "2_2") (pintype "passive"))
      (node (ref "R21") (pin "2") (pinfunction "2_2") (pintype "passive"))
      (node (ref "R22") (pin "2") (pinfunction "2_2") (pintype "passive"))
      (node (ref "R23") (pin "2") (pinfunction "2_2") (pintype "passive"))
      (node (ref "R25") (pin "2") (pinfunction "2_2") (pintype "passive"))
      (node (ref "R26") (pin "2") (pinfunction "2_2") (pintype "passive"))
      (node (ref "R28") (pin "2") (pinfunction "2_2") (pintype "passive"))
      (node (ref "R3") (pin "2") (pinfunction "2_2") (pintype "passive"))
      (node (ref "R4") (pin "2") (pinfunction "2_2") (pintype "passive"))
      (node (ref "R5") (pin "2") (pinfunction "2_2") (pintype "passive"))
      (node (ref "R6") (pin "2") (pinfunction "2_2") (pintype "passive"))
      (node (ref "R7") (pin "2") (pinfunction "2_2") (pintype "passive"))
      (node (ref "R8") (pin "2") (pinfunction "2_2") (pintype "passive"))
      (node (ref "R9") (pin "2") (pinfunction "2_2") (pintype "passive"))
    )
    (net (code "73") (name "DDR1V5") (class "Default")
      (node (ref "C1") (pin "2") (pinfunction "2_2") (pintype "passive"))
      (node (ref "C10") (pin "2") (pinfunction "2_2") (pintype "passive"))
      (node (ref "C11") (pin "2") (pinfunction "2_2") (pintype "passive"))
      (node (ref "C14") (pin "2") (pinfunction "2_2") (pintype "passive"))
      (node (ref "C15") (pin "2") (pinfunction "2_2") (pintype "passive"))
      (node (ref "C16") (pin "2") (pinfunction "2_2") (pintype "passive"))
      (node (ref "C17") (pin "2") (pinfunction "2_2") (pintype "passive"))
      (node (ref "C18") (pin "2") (pinfunction "2_2") (pintype "passive"))
      (node (ref "C19") (pin "2") (pinfunction "2_2") (pintype "passive"))
      (node (ref "C2") (pin "2") (pinfunction "2_2") (pintype "passive"))
      (node (ref "C20") (pin "2") (pinfunction "2_2") (pintype "passive"))
      (node (ref "C21") (pin "2") (pinfunction "2_2") (pintype "passive"))
      (node (ref "C22") (pin "2") (pinfunction "2_2") (pintype "passive"))
      (node (ref "C23") (pin "2") (pinfunction "2_2") (pintype "passive"))
      (node (ref "C24") (pin "2") (pinfunction "2_2") (pintype "passive"))
      (node (ref "C25") (pin "2") (pinfunction "2_2") (pintype "passive"))
      (node (ref "C26") (pin "2") (pinfunction "2_2") (pintype "passive"))
      (node (ref "C27") (pin "2") (pinfunction "2_2") (pintype "passive"))
      (node (ref "C28") (pin "2") (pinfunction "2_2") (pintype "passive"))
      (node (ref "C29") (pin "2") (pinfunction "2_2") (pintype "passive"))
      (node (ref "C3") (pin "2") (pinfunction "2_2") (pintype "passive"))
      (node (ref "C30") (pin "2") (pinfunction "2_2") (pintype "passive"))
      (node (ref "C31") (pin "2") (pinfunction "2_2") (pintype "passive"))
      (node (ref "C32") (pin "2") (pinfunction "2_2") (pintype "passive"))
      (node (ref "C33") (pin "2") (pinfunction "2_2") (pintype "passive"))
      (node (ref "C34") (pin "2") (pinfunction "2_2") (pintype "passive"))
      (node (ref "C35") (pin "2") (pinfunction "2_2") (pintype "passive"))
      (node (ref "C36") (pin "2") (pinfunction "2_2") (pintype "passive"))
      (node (ref "C37") (pin "2") (pinfunction "2_2") (pintype "passive"))
      (node (ref "C38") (pin "2") (pinfunction "2_2") (pintype "passive"))
      (node (ref "C39") (pin "2") (pinfunction "2_2") (pintype "passive"))
      (node (ref "C4") (pin "2") (pinfunction "2_2") (pintype "passive"))
      (node (ref "C40") (pin "2") (pinfunction "2_2") (pintype "passive"))
      (node (ref "C41") (pin "2") (pinfunction "2_2") (pintype "passive"))
      (node (ref "C42") (pin "2") (pinfunction "2_2") (pintype "passive"))
      (node (ref "C43") (pin "2") (pinfunction "2_2") (pintype "passive"))
      (node (ref "C44") (pin "2") (pinfunction "2_2") (pintype "passive"))
      (node (ref "C45") (pin "2") (pinfunction "2_2") (pintype "passive"))
      (node (ref "C46") (pin "2") (pinfunction "2_2") (pintype "passive"))
      (node (ref "C47") (pin "2") (pinfunction "2_2") (pintype "passive"))
      (node (ref "C5") (pin "2") (pinfunction "2_2") (pintype "passive"))
      (node (ref "C50") (pin "2") (pinfunction "2_2") (pintype "passive"))
      (node (ref "C51") (pin "2") (pinfunction "2_2") (pintype "passive"))
      (node (ref "C52") (pin "2") (pinfunction "2_2") (pintype "passive"))
      (node (ref "C53") (pin "2") (pinfunction "2_2") (pintype "passive"))
      (node (ref "C54") (pin "2") (pinfunction "2_2") (pintype "passive"))
      (node (ref "C55") (pin "2") (pinfunction "2_2") (pintype "passive"))
      (node (ref "C6") (pin "2") (pinfunction "2_2") (pintype "passive"))
      (node (ref "C7") (pin "2") (pinfunction "2_2") (pintype "passive"))
      (node (ref "C8") (pin "2") (pinfunction "2_2") (pintype "passive"))
      (node (ref "C9") (pin "2") (pinfunction "2_2") (pintype "passive"))
      (node (ref "FB1") (pin "1") (pinfunction "1_1") (pintype "passive"))
      (node (ref "R27") (pin "2") (pinfunction "2_2") (pintype "passive"))
      (node (ref "U10") (pin "A1") (pinfunction "VDDQ_A1") (pintype "power_in"))
      (node (ref "U10") (pin "A8") (pinfunction "VDDQ_A8") (pintype "power_in"))
      (node (ref "U10") (pin "B2") (pinfunction "VDD_B2") (pintype "power_in"))
      (node (ref "U10") (pin "C1") (pinfunction "VDDQ_C1") (pintype "power_in"))
      (node (ref "U10") (pin "C9") (pinfunction "VDDQ_C9") (pintype "power_in"))
      (node (ref "U10") (pin "D2") (pinfunction "VDDQ_D2") (pintype "power_in"))
      (node (ref "U10") (pin "D9") (pinfunction "VDD_D9") (pintype "power_in"))
      (node (ref "U10") (pin "E9") (pinfunction "VDDQ_E9") (pintype "power_in"))
      (node (ref "U10") (pin "F1") (pinfunction "VDDQ_F1") (pintype "power_in"))
      (node (ref "U10") (pin "G7") (pinfunction "VDD_G7") (pintype "power_in"))
      (node (ref "U10") (pin "H2") (pinfunction "VDDQ_H2") (pintype "power_in"))
      (node (ref "U10") (pin "H9") (pinfunction "VDDQ_H9") (pintype "power_in"))
      (node (ref "U10") (pin "K2") (pinfunction "VDD_K2") (pintype "power_in"))
      (node (ref "U10") (pin "K8") (pinfunction "VDD_K8") (pintype "power_in"))
      (node (ref "U10") (pin "N1") (pinfunction "VDD_N1") (pintype "power_in"))
      (node (ref "U10") (pin "N9") (pinfunction "VDD_N9") (pintype "power_in"))
      (node (ref "U10") (pin "R1") (pinfunction "VDD_R1") (pintype "power_in"))
      (node (ref "U10") (pin "R9") (pinfunction "VDD_R9") (pintype "power_in"))
      (node (ref "U11") (pin "A1") (pinfunction "VDDQ_A1") (pintype "power_in"))
      (node (ref "U11") (pin "A8") (pinfunction "VDDQ_A8") (pintype "power_in"))
      (node (ref "U11") (pin "B2") (pinfunction "VDD_B2") (pintype "power_in"))
      (node (ref "U11") (pin "C1") (pinfunction "VDDQ_C1") (pintype "power_in"))
      (node (ref "U11") (pin "C9") (pinfunction "VDDQ_C9") (pintype "power_in"))
      (node (ref "U11") (pin "D2") (pinfunction "VDDQ_D2") (pintype "power_in"))
      (node (ref "U11") (pin "D9") (pinfunction "VDD_D9") (pintype "power_in"))
      (node (ref "U11") (pin "E9") (pinfunction "VDDQ_E9") (pintype "power_in"))
      (node (ref "U11") (pin "F1") (pinfunction "VDDQ_F1") (pintype "power_in"))
      (node (ref "U11") (pin "G7") (pinfunction "VDD_G7") (pintype "power_in"))
      (node (ref "U11") (pin "H2") (pinfunction "VDDQ_H2") (pintype "power_in"))
      (node (ref "U11") (pin "H9") (pinfunction "VDDQ_H9") (pintype "power_in"))
      (node (ref "U11") (pin "K2") (pinfunction "VDD_K2") (pintype "power_in"))
      (node (ref "U11") (pin "K8") (pinfunction "VDD_K8") (pintype "power_in"))
      (node (ref "U11") (pin "N1") (pinfunction "VDD_N1") (pintype "power_in"))
      (node (ref "U11") (pin "N9") (pinfunction "VDD_N9") (pintype "power_in"))
      (node (ref "U11") (pin "R1") (pinfunction "VDD_R1") (pintype "power_in"))
      (node (ref "U11") (pin "R9") (pinfunction "VDD_R9") (pintype "power_in"))
    )
    (net (code "74") (name "DDRVREF") (class "Default")
      (node (ref "C12") (pin "2") (pinfunction "2_2") (pintype "passive"))
      (node (ref "C13") (pin "2") (pinfunction "2_2") (pintype "passive"))
      (node (ref "C38") (pin "1") (pinfunction "1_1") (pintype "passive"))
      (node (ref "C39") (pin "1") (pinfunction "1_1") (pintype "passive"))
      (node (ref "C48") (pin "2") (pinfunction "2_2") (pintype "passive"))
      (node (ref "C49") (pin "2") (pinfunction "2_2") (pintype "passive"))
      (node (ref "U1") (pin "H7") (pinfunction "PS_DDR_VREF0_502_H7") (pintype "input"))
      (node (ref "U1") (pin "P7") (pinfunction "PS_DDR_VREF1_502_P7") (pintype "input"))
      (node (ref "U10") (pin "H1") (pinfunction "VREFDQ_H1") (pintype "input"))
      (node (ref "U10") (pin "M8") (pinfunction "VREFCA_M8") (pintype "input"))
      (node (ref "U11") (pin "H1") (pinfunction "VREFDQ_H1") (pintype "input"))
      (node (ref "U11") (pin "M8") (pinfunction "VREFCA_M8") (pintype "input"))
    )
    (net (code "75") (name "GND") (class "Default")
      (node (ref "C12") (pin "1") (pinfunction "1_1") (pintype "passive"))
      (node (ref "C13") (pin "1") (pinfunction "1_1") (pintype "passive"))
      (node (ref "C14") (pin "1") (pinfunction "1_1") (pintype "passive"))
      (node (ref "C15") (pin "1") (pinfunction "1_1") (pintype "passive"))
      (node (ref "C16") (pin "1") (pinfunction "1_1") (pintype "passive"))
      (node (ref "C17") (pin "1") (pinfunction "1_1") (pintype "passive"))
      (node (ref "C18") (pin "1") (pinfunction "1_1") (pintype "passive"))
      (node (ref "C19") (pin "1") (pinfunction "1_1") (pintype "passive"))
      (node (ref "C20") (pin "1") (pinfunction "1_1") (pintype "passive"))
      (node (ref "C21") (pin "1") (pinfunction "1_1") (pintype "passive"))
      (node (ref "C22") (pin "1") (pinfunction "1_1") (pintype "passive"))
      (node (ref "C23") (pin "1") (pinfunction "1_1") (pintype "passive"))
      (node (ref "C24") (pin "1") (pinfunction "1_1") (pintype "passive"))
      (node (ref "C25") (pin "1") (pinfunction "1_1") (pintype "passive"))
      (node (ref "C26") (pin "1") (pinfunction "1_1") (pintype "passive"))
      (node (ref "C27") (pin "1") (pinfunction "1_1") (pintype "passive"))
      (node (ref "C28") (pin "1") (pinfunction "1_1") (pintype "passive"))
      (node (ref "C29") (pin "1") (pinfunction "1_1") (pintype "passive"))
      (node (ref "C30") (pin "1") (pinfunction "1_1") (pintype "passive"))
      (node (ref "C31") (pin "1") (pinfunction "1_1") (pintype "passive"))
      (node (ref "C32") (pin "1") (pinfunction "1_1") (pintype "passive"))
      (node (ref "C33") (pin "1") (pinfunction "1_1") (pintype "passive"))
      (node (ref "C34") (pin "1") (pinfunction "1_1") (pintype "passive"))
      (node (ref "C35") (pin "1") (pinfunction "1_1") (pintype "passive"))
      (node (ref "C36") (pin "1") (pinfunction "1_1") (pintype "passive"))
      (node (ref "C37") (pin "1") (pinfunction "1_1") (pintype "passive"))
      (node (ref "C40") (pin "1") (pinfunction "1_1") (pintype "passive"))
      (node (ref "C41") (pin "1") (pinfunction "1_1") (pintype "passive"))
      (node (ref "C42") (pin "1") (pinfunction "1_1") (pintype "passive"))
      (node (ref "C43") (pin "1") (pinfunction "1_1") (pintype "passive"))
      (node (ref "C44") (pin "1") (pinfunction "1_1") (pintype "passive"))
      (node (ref "C45") (pin "1") (pinfunction "1_1") (pintype "passive"))
      (node (ref "C46") (pin "1") (pinfunction "1_1") (pintype "passive"))
      (node (ref "C47") (pin "1") (pinfunction "1_1") (pintype "passive"))
      (node (ref "C48") (pin "1") (pinfunction "1_1") (pintype "passive"))
      (node (ref "C49") (pin "1") (pinfunction "1_1") (pintype "passive"))
      (node (ref "C50") (pin "1") (pinfunction "1_1") (pintype "passive"))
      (node (ref "C51") (pin "1") (pinfunction "1_1") (pintype "passive"))
      (node (ref "C52") (pin "1") (pinfunction "1_1") (pintype "passive"))
      (node (ref "C53") (pin "1") (pinfunction "1_1") (pintype "passive"))
      (node (ref "C54") (pin "1") (pinfunction "1_1") (pintype "passive"))
      (node (ref "C55") (pin "1") (pinfunction "1_1") (pintype "passive"))
      (node (ref "R10") (pin "2") (pinfunction "2_2") (pintype "passive"))
      (node (ref "R2") (pin "2") (pinfunction "2_2") (pintype "passive"))
      (node (ref "R24") (pin "2") (pinfunction "2_2") (pintype "passive"))
      (node (ref "R29") (pin "2") (pinfunction "2_2") (pintype "passive"))
      (node (ref "U10") (pin "A9") (pinfunction "VSS_A9") (pintype "power_in"))
      (node (ref "U10") (pin "B1") (pinfunction "VSSQ_B1") (pintype "power_in"))
      (node (ref "U10") (pin "B3") (pinfunction "VSS_B3") (pintype "power_in"))
      (node (ref "U10") (pin "B9") (pinfunction "VSSQ_B9") (pintype "power_in"))
      (node (ref "U10") (pin "D1") (pinfunction "VSSQ_D1") (pintype "power_in"))
      (node (ref "U10") (pin "D8") (pinfunction "VSSQ_D8") (pintype "power_in"))
      (node (ref "U10") (pin "E1") (pinfunction "VSS_E1") (pintype "power_in"))
      (node (ref "U10") (pin "E2") (pinfunction "VSSQ_E2") (pintype "power_in"))
      (node (ref "U10") (pin "E8") (pinfunction "VSSQ_E8") (pintype "power_in"))
      (node (ref "U10") (pin "F9") (pinfunction "VSSQ_F9") (pintype "power_in"))
      (node (ref "U10") (pin "G1") (pinfunction "VSSQ_G1") (pintype "power_in"))
      (node (ref "U10") (pin "G8") (pinfunction "VSS_G8") (pintype "power_in"))
      (node (ref "U10") (pin "G9") (pinfunction "VSSQ_G9") (pintype "power_in"))
      (node (ref "U10") (pin "J2") (pinfunction "VSS_J2") (pintype "power_in"))
      (node (ref "U10") (pin "J8") (pinfunction "VSS_J8") (pintype "power_in"))
      (node (ref "U10") (pin "M1") (pinfunction "VSS_M1") (pintype "power_in"))
      (node (ref "U10") (pin "M9") (pinfunction "VSS_M9") (pintype "power_in"))
      (node (ref "U10") (pin "P1") (pinfunction "VSS_P1") (pintype "power_in"))
      (node (ref "U10") (pin "P9") (pinfunction "VSS_P9") (pintype "power_in"))
      (node (ref "U10") (pin "T1") (pinfunction "VSS_T1") (pintype "power_in"))
      (node (ref "U10") (pin "T9") (pinfunction "VSS_T9") (pintype "power_in"))
      (node (ref "U11") (pin "A9") (pinfunction "VSS_A9") (pintype "power_in"))
      (node (ref "U11") (pin "B1") (pinfunction "VSSQ_B1") (pintype "power_in"))
      (node (ref "U11") (pin "B3") (pinfunction "VSS_B3") (pintype "power_in"))
      (node (ref "U11") (pin "B9") (pinfunction "VSSQ_B9") (pintype "power_in"))
      (node (ref "U11") (pin "D1") (pinfunction "VSSQ_D1") (pintype "power_in"))
      (node (ref "U11") (pin "D8") (pinfunction "VSSQ_D8") (pintype "power_in"))
      (node (ref "U11") (pin "E1") (pinfunction "VSS_E1") (pintype "power_in"))
      (node (ref "U11") (pin "E2") (pinfunction "VSSQ_E2") (pintype "power_in"))
      (node (ref "U11") (pin "E8") (pinfunction "VSSQ_E8") (pintype "power_in"))
      (node (ref "U11") (pin "F9") (pinfunction "VSSQ_F9") (pintype "power_in"))
      (node (ref "U11") (pin "G1") (pinfunction "VSSQ_G1") (pintype "power_in"))
      (node (ref "U11") (pin "G8") (pinfunction "VSS_G8") (pintype "power_in"))
      (node (ref "U11") (pin "G9") (pinfunction "VSSQ_G9") (pintype "power_in"))
      (node (ref "U11") (pin "J2") (pinfunction "VSS_J2") (pintype "power_in"))
      (node (ref "U11") (pin "J8") (pinfunction "VSS_J8") (pintype "power_in"))
      (node (ref "U11") (pin "M1") (pinfunction "VSS_M1") (pintype "power_in"))
      (node (ref "U11") (pin "M9") (pinfunction "VSS_M9") (pintype "power_in"))
      (node (ref "U11") (pin "P1") (pinfunction "VSS_P1") (pintype "power_in"))
      (node (ref "U11") (pin "P9") (pinfunction "VSS_P9") (pintype "power_in"))
      (node (ref "U11") (pin "T1") (pinfunction "VSS_T1") (pintype "power_in"))
      (node (ref "U11") (pin "T9") (pinfunction "VSS_T9") (pintype "power_in"))
    )
    (net (code "76") (name "Net-(U1G-PS_DDR_VRN_502)") (class "Default")
      (node (ref "R27") (pin "1") (pinfunction "1_1") (pintype "passive"))
      (node (ref "U1") (pin "M7") (pinfunction "PS_DDR_VRN_502_M7") (pintype "output"))
    )
    (net (code "77") (name "Net-(U1G-PS_DDR_VRP_502)") (class "Default")
      (node (ref "R24") (pin "1") (pinfunction "1_1") (pintype "passive"))
      (node (ref "U1") (pin "N7") (pinfunction "PS_DDR_VRP_502_N7") (pintype "output"))
    )
    (net (code "78") (name "Net-(U10A-ZQ)") (class "Default")
      (node (ref "R10") (pin "1") (pinfunction "1_1") (pintype "passive"))
      (node (ref "U10") (pin "L8") (pinfunction "ZQ_L8") (pintype "input"))
    )
    (net (code "79") (name "Net-(U11A-ZQ)") (class "Default")
      (node (ref "R29") (pin "1") (pinfunction "1_1") (pintype "passive"))
      (node (ref "U11") (pin "L8") (pinfunction "ZQ_L8") (pintype "input"))
    )
    (net (code "80") (name "VCC1V5") (class "Default")
      (node (ref "FB1") (pin "2") (pinfunction "2_2") (pintype "passive"))
    )
    (net (code "81") (name "unconnected-(U10C-NC-PadJ1)") (class "Default")
      (node (ref "U10") (pin "J1") (pinfunction "NC_J1") (pintype "passive"))
    )
    (net (code "82") (name "unconnected-(U10C-NC-PadJ9)") (class "Default")
      (node (ref "U10") (pin "J9") (pinfunction "NC_J9") (pintype "passive"))
    )
    (net (code "83") (name "unconnected-(U10C-NC-PadL1)") (class "Default")
      (node (ref "U10") (pin "L1") (pinfunction "NC_L1") (pintype "passive"))
    )
    (net (code "84") (name "unconnected-(U10C-NC-PadL9)") (class "Default")
      (node (ref "U10") (pin "L9") (pinfunction "NC_L9") (pintype "passive"))
    )
    (net (code "85") (name "unconnected-(U10C-NC-PadM7)") (class "Default")
      (node (ref "U10") (pin "M7") (pinfunction "NC_M7") (pintype "passive"))
    )
    (net (code "86") (name "unconnected-(U11C-NC-PadJ1)") (class "Default")
      (node (ref "U11") (pin "J1") (pinfunction "NC_J1") (pintype "passive"))
    )
    (net (code "87") (name "unconnected-(U11C-NC-PadJ9)") (class "Default")
      (node (ref "U11") (pin "J9") (pinfunction "NC_J9") (pintype "passive"))
    )
    (net (code "88") (name "unconnected-(U11C-NC-PadL1)") (class "Default")
      (node (ref "U11") (pin "L1") (pinfunction "NC_L1") (pintype "passive"))
    )
    (net (code "89") (name "unconnected-(U11C-NC-PadL9)") (class "Default")
      (node (ref "U11") (pin "L9") (pinfunction "NC_L9") (pintype "passive"))
    )
    (net (code "90") (name "unconnected-(U11C-NC-PadM7)") (class "Default")
      (node (ref "U11") (pin "M7") (pinfunction "NC_M7") (pintype "passive"))
    )
  )
)
